# motor-shield.net
KiCad netlist of a schematic drawn in EAGLE
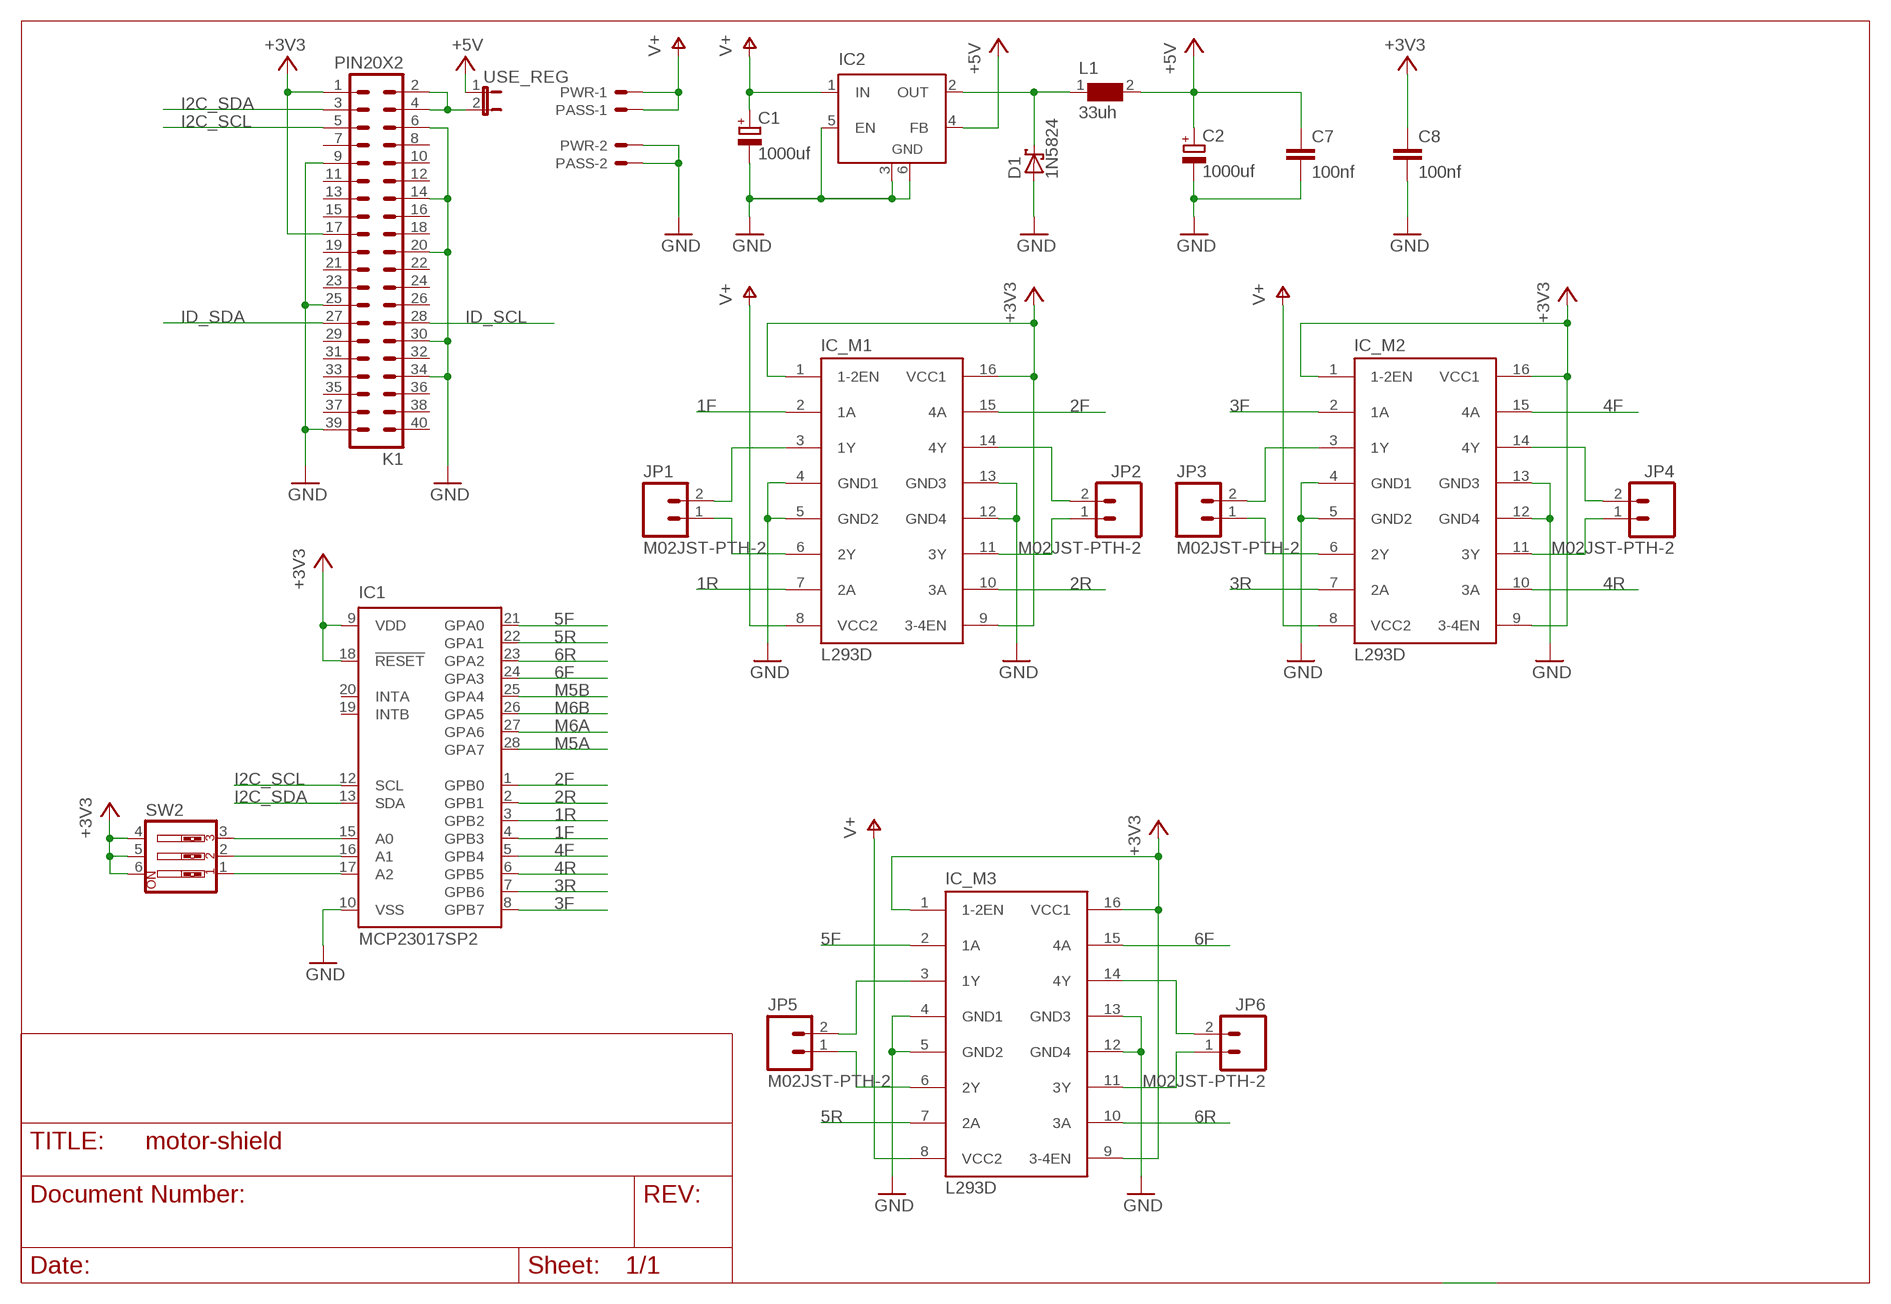
[diagram p0: schematic, sheet 1]

(export (version "E")
  (design (tool "Eeschema 10.0.6"))
  (components
    (comp (ref "C1")
      (value "1000uf")
      (footprint "eagle-import:E2,5-6")
      (libsource (lib "eagle-import") (part "CPOL-EUE2.5-6"))
    )
    (comp (ref "C2")
      (value "1000uf")
      (footprint "eagle-import:E2,5-7")
      (libsource (lib "eagle-import") (part "CPOL-EUE2.5-7"))
    )
    (comp (ref "C7")
      (value "100nf")
      (footprint "eagle-import:C025-030X050")
      (libsource (lib "eagle-import") (part "C-EU025-030X050"))
    )
    (comp (ref "C8")
      (value "100nf")
      (footprint "eagle-import:C025-030X050")
      (libsource (lib "eagle-import") (part "C-EU025-030X050"))
    )
    (comp (ref "D1")
      (value "1N5824")
      (footprint "eagle-import:DO41-7.6")
      (libsource (lib "eagle-import") (part "1N5817-B"))
    )
    (comp (ref "IC1")
      (value "MCP23017SP2")
      (footprint "eagle-import:DIL28-3-ROUND")
      (libsource (lib "eagle-import") (part "MCP23017SP2"))
    )
    (comp (ref "IC2")
      (value "LM2596S")
      (footprint "eagle-import:TO263-5")
      (libsource (lib "eagle-import") (part "LM2596S"))
    )
    (comp (ref "IC_M1")
      (value "L293D")
      (footprint "eagle-import:DIL16")
      (libsource (lib "eagle-import") (part "L293D"))
    )
    (comp (ref "IC_M2")
      (value "L293D")
      (footprint "eagle-import:DIL16")
      (libsource (lib "eagle-import") (part "L293D"))
    )
    (comp (ref "IC_M3")
      (value "L293D")
      (footprint "eagle-import:DIL16")
      (libsource (lib "eagle-import") (part "L293D"))
    )
    (comp (ref "JP1")
      (value "M02JST-PTH-2")
      (footprint "eagle-import:JST-2-PTH")
      (libsource (lib "eagle-import") (part "M02JST-PTH-2"))
    )
    (comp (ref "JP2")
      (value "M02JST-PTH-2")
      (footprint "eagle-import:JST-2-PTH")
      (libsource (lib "eagle-import") (part "M02JST-PTH-2"))
    )
    (comp (ref "JP3")
      (value "M02JST-PTH-2")
      (footprint "eagle-import:JST-2-PTH")
      (libsource (lib "eagle-import") (part "M02JST-PTH-2"))
    )
    (comp (ref "JP4")
      (value "M02JST-PTH-2")
      (footprint "eagle-import:JST-2-PTH")
      (libsource (lib "eagle-import") (part "M02JST-PTH-2"))
    )
    (comp (ref "JP5")
      (value "M02JST-PTH-2")
      (footprint "eagle-import:JST-2-PTH")
      (libsource (lib "eagle-import") (part "M02JST-PTH-2"))
    )
    (comp (ref "JP6")
      (value "M02JST-PTH-2")
      (footprint "eagle-import:JST-2-PTH")
      (libsource (lib "eagle-import") (part "M02JST-PTH-2"))
    )
    (comp (ref "K1")
      (value "PIN20X2")
      (footprint "eagle-import:PIN_20X2")
      (libsource (lib "eagle-import") (part "PIN20X2"))
    )
    (comp (ref "L1")
      (value "33uh")
      (footprint "eagle-import:WE-PD_1260_1245_1280_1210")
      (fields (field (name "MPN") "744770133"))
      (libsource (lib "eagle-import") (part "WE-PD_1260/1245/1280/1210-744770133"))
    )
    (comp (ref "PASS")
      (value "22-05-7028-02")
      (footprint "eagle-import:7395-02")
      (libsource (lib "eagle-import") (part "22-?-0205-7028"))
    )
    (comp (ref "PWR")
      (value "22-05-7028-02")
      (footprint "eagle-import:7395-02")
      (libsource (lib "eagle-import") (part "22-?-0205-7028"))
    )
    (comp (ref "SW2")
      (value "SW_DIP-3")
      (footprint "eagle-import:EDG-03")
      (libsource (lib "eagle-import") (part "SW_DIP-3"))
    )
    (comp (ref "USE_REG")
      (value "JP1E")
      (footprint "eagle-import:JP1")
      (libsource (lib "eagle-import") (part "JP1E"))
    )
  )
  (nets
    (net (code "1") (name "+3V3") (class "Default")
      (node (ref "C8") (pin "1") (pinfunction "1_1") (pintype "passive"))
      (node (ref "IC1") (pin "18") (pinfunction "~{RESET}_18") (pintype "input"))
      (node (ref "IC1") (pin "9") (pinfunction "VDD_9") (pintype "power_in"))
      (node (ref "IC_M1") (pin "1") (pinfunction "1-2EN_1") (pintype "input"))
      (node (ref "IC_M1") (pin "16") (pinfunction "VCC1_16") (pintype "power_in"))
      (node (ref "IC_M1") (pin "9") (pinfunction "3-4EN_9") (pintype "input"))
      (node (ref "IC_M2") (pin "1") (pinfunction "1-2EN_1") (pintype "input"))
      (node (ref "IC_M2") (pin "16") (pinfunction "VCC1_16") (pintype "power_in"))
      (node (ref "IC_M2") (pin "9") (pinfunction "3-4EN_9") (pintype "input"))
      (node (ref "IC_M3") (pin "1") (pinfunction "1-2EN_1") (pintype "input"))
      (node (ref "IC_M3") (pin "16") (pinfunction "VCC1_16") (pintype "power_in"))
      (node (ref "IC_M3") (pin "9") (pinfunction "3-4EN_9") (pintype "input"))
      (node (ref "K1") (pin "1") (pinfunction "1_1") (pintype "passive"))
      (node (ref "K1") (pin "17") (pinfunction "17_17") (pintype "passive"))
      (node (ref "SW2") (pin "4") (pinfunction "4_4") (pintype "passive"))
      (node (ref "SW2") (pin "5") (pinfunction "5_5") (pintype "passive"))
      (node (ref "SW2") (pin "6") (pinfunction "6_6") (pintype "passive"))
    )
    (net (code "2") (name "+5V") (class "Default")
      (node (ref "C2") (pin "+") (pinfunction "+_+") (pintype "passive"))
      (node (ref "C7") (pin "1") (pinfunction "1_1") (pintype "passive"))
      (node (ref "IC2") (pin "4") (pinfunction "FB_4") (pintype "input"))
      (node (ref "L1") (pin "2") (pinfunction "2_2") (pintype "passive"))
      (node (ref "USE_REG") (pin "1") (pinfunction "1_1") (pintype "passive"))
    )
    (net (code "3") (name "/1F") (class "Default")
      (node (ref "IC1") (pin "4") (pinfunction "GPB3_4") (pintype "bidirectional"))
      (node (ref "IC_M1") (pin "2") (pinfunction "1A_2") (pintype "input"))
    )
    (net (code "4") (name "/1R") (class "Default")
      (node (ref "IC1") (pin "3") (pinfunction "GPB2_3") (pintype "bidirectional"))
      (node (ref "IC_M1") (pin "7") (pinfunction "2A_7") (pintype "input"))
    )
    (net (code "5") (name "/2F") (class "Default")
      (node (ref "IC1") (pin "1") (pinfunction "GPB0_1") (pintype "bidirectional"))
      (node (ref "IC_M1") (pin "15") (pinfunction "4A_15") (pintype "input"))
    )
    (net (code "6") (name "/2R") (class "Default")
      (node (ref "IC1") (pin "2") (pinfunction "GPB1_2") (pintype "bidirectional"))
      (node (ref "IC_M1") (pin "10") (pinfunction "3A_10") (pintype "input"))
    )
    (net (code "7") (name "/3F") (class "Default")
      (node (ref "IC1") (pin "8") (pinfunction "GPB7_8") (pintype "bidirectional"))
      (node (ref "IC_M2") (pin "2") (pinfunction "1A_2") (pintype "input"))
    )
    (net (code "8") (name "/3R") (class "Default")
      (node (ref "IC1") (pin "7") (pinfunction "GPB6_7") (pintype "bidirectional"))
      (node (ref "IC_M2") (pin "7") (pinfunction "2A_7") (pintype "input"))
    )
    (net (code "9") (name "/4F") (class "Default")
      (node (ref "IC1") (pin "5") (pinfunction "GPB4_5") (pintype "bidirectional"))
      (node (ref "IC_M2") (pin "15") (pinfunction "4A_15") (pintype "input"))
    )
    (net (code "10") (name "/4R") (class "Default")
      (node (ref "IC1") (pin "6") (pinfunction "GPB5_6") (pintype "bidirectional"))
      (node (ref "IC_M2") (pin "10") (pinfunction "3A_10") (pintype "input"))
    )
    (net (code "11") (name "/5F") (class "Default")
      (node (ref "IC1") (pin "21") (pinfunction "GPA0_21") (pintype "bidirectional"))
      (node (ref "IC_M3") (pin "2") (pinfunction "1A_2") (pintype "input"))
    )
    (net (code "12") (name "/5R") (class "Default")
      (node (ref "IC1") (pin "22") (pinfunction "GPA1_22") (pintype "bidirectional"))
      (node (ref "IC_M3") (pin "7") (pinfunction "2A_7") (pintype "input"))
    )
    (net (code "13") (name "/6F") (class "Default")
      (node (ref "IC1") (pin "24") (pinfunction "GPA3_24") (pintype "bidirectional"))
      (node (ref "IC_M3") (pin "15") (pinfunction "4A_15") (pintype "input"))
    )
    (net (code "14") (name "/6R") (class "Default")
      (node (ref "IC1") (pin "23") (pinfunction "GPA2_23") (pintype "bidirectional"))
      (node (ref "IC_M3") (pin "10") (pinfunction "3A_10") (pintype "input"))
    )
    (net (code "15") (name "/I2C_SCL") (class "Default")
      (node (ref "IC1") (pin "12") (pinfunction "SCL_12") (pintype "input"))
      (node (ref "K1") (pin "5") (pinfunction "5_5") (pintype "passive"))
    )
    (net (code "16") (name "/I2C_SDA") (class "Default")
      (node (ref "IC1") (pin "13") (pinfunction "SDA_13") (pintype "bidirectional"))
      (node (ref "K1") (pin "3") (pinfunction "3_3") (pintype "passive"))
    )
    (net (code "17") (name "/ID_SCL") (class "Default")
      (node (ref "K1") (pin "28") (pinfunction "28_28") (pintype "passive"))
    )
    (net (code "18") (name "/ID_SDA") (class "Default")
      (node (ref "K1") (pin "27") (pinfunction "27_27") (pintype "passive"))
    )
    (net (code "19") (name "/M5A") (class "Default")
      (node (ref "IC1") (pin "28") (pinfunction "GPA7_28") (pintype "bidirectional"))
    )
    (net (code "20") (name "/M5B") (class "Default")
      (node (ref "IC1") (pin "25") (pinfunction "GPA4_25") (pintype "bidirectional"))
    )
    (net (code "21") (name "/M6A") (class "Default")
      (node (ref "IC1") (pin "27") (pinfunction "GPA6_27") (pintype "bidirectional"))
    )
    (net (code "22") (name "/M6B") (class "Default")
      (node (ref "IC1") (pin "26") (pinfunction "GPA5_26") (pintype "bidirectional"))
    )
    (net (code "23") (name "GND") (class "Default")
      (node (ref "C1") (pin "-") (pinfunction "-_-") (pintype "passive"))
      (node (ref "C2") (pin "-") (pinfunction "-_-") (pintype "passive"))
      (node (ref "C7") (pin "2") (pinfunction "2_2") (pintype "passive"))
      (node (ref "C8") (pin "2") (pinfunction "2_2") (pintype "passive"))
      (node (ref "D1") (pin "A") (pinfunction "A_A") (pintype "passive"))
      (node (ref "IC1") (pin "10") (pinfunction "VSS_10") (pintype "power_in"))
      (node (ref "IC2") (pin "3") (pinfunction "GND_3") (pintype "power_in"))
      (node (ref "IC2") (pin "5") (pinfunction "EN_5") (pintype "input"))
      (node (ref "IC2") (pin "6") (pinfunction "GND_6") (pintype "power_in"))
      (node (ref "IC_M1") (pin "12") (pinfunction "GND4_12") (pintype "power_in"))
      (node (ref "IC_M1") (pin "13") (pinfunction "GND3_13") (pintype "power_in"))
      (node (ref "IC_M1") (pin "4") (pinfunction "GND1_4") (pintype "power_in"))
      (node (ref "IC_M1") (pin "5") (pinfunction "GND2_5") (pintype "power_in"))
      (node (ref "IC_M2") (pin "12") (pinfunction "GND4_12") (pintype "power_in"))
      (node (ref "IC_M2") (pin "13") (pinfunction "GND3_13") (pintype "power_in"))
      (node (ref "IC_M2") (pin "4") (pinfunction "GND1_4") (pintype "power_in"))
      (node (ref "IC_M2") (pin "5") (pinfunction "GND2_5") (pintype "power_in"))
      (node (ref "IC_M3") (pin "12") (pinfunction "GND4_12") (pintype "power_in"))
      (node (ref "IC_M3") (pin "13") (pinfunction "GND3_13") (pintype "power_in"))
      (node (ref "IC_M3") (pin "4") (pinfunction "GND1_4") (pintype "power_in"))
      (node (ref "IC_M3") (pin "5") (pinfunction "GND2_5") (pintype "power_in"))
      (node (ref "K1") (pin "14") (pinfunction "14_14") (pintype "passive"))
      (node (ref "K1") (pin "20") (pinfunction "20_20") (pintype "passive"))
      (node (ref "K1") (pin "25") (pinfunction "25_25") (pintype "passive"))
      (node (ref "K1") (pin "30") (pinfunction "30_30") (pintype "passive"))
      (node (ref "K1") (pin "34") (pinfunction "34_34") (pintype "passive"))
      (node (ref "K1") (pin "39") (pinfunction "39_39") (pintype "passive"))
      (node (ref "K1") (pin "6") (pinfunction "6_6") (pintype "passive"))
      (node (ref "K1") (pin "9") (pinfunction "9_9") (pintype "passive"))
      (node (ref "PASS") (pin "2") (pinfunction "S_2") (pintype "passive"))
      (node (ref "PWR") (pin "2") (pinfunction "S_2") (pintype "passive"))
    )
    (net (code "24") (name "Net-(IC1-A0)") (class "Default")
      (node (ref "IC1") (pin "15") (pinfunction "A0_15") (pintype "input"))
      (node (ref "SW2") (pin "3") (pinfunction "3_3") (pintype "passive"))
    )
    (net (code "25") (name "Net-(IC1-A1)") (class "Default")
      (node (ref "IC1") (pin "16") (pinfunction "A1_16") (pintype "input"))
      (node (ref "SW2") (pin "2") (pinfunction "2_2") (pintype "passive"))
    )
    (net (code "26") (name "Net-(IC1-A2)") (class "Default")
      (node (ref "IC1") (pin "17") (pinfunction "A2_17") (pintype "input"))
      (node (ref "SW2") (pin "1") (pinfunction "1_1") (pintype "passive"))
    )
    (net (code "27") (name "Net-(IC2-OUT)") (class "Default")
      (node (ref "D1") (pin "C") (pinfunction "C_C") (pintype "passive"))
      (node (ref "IC2") (pin "2") (pinfunction "OUT_2") (pintype "output"))
      (node (ref "L1") (pin "1") (pinfunction "1_1") (pintype "passive"))
    )
    (net (code "28") (name "Net-(IC_M1-1Y)") (class "Default")
      (node (ref "IC_M1") (pin "3") (pinfunction "1Y_3") (pintype "output"))
      (node (ref "JP1") (pin "2") (pinfunction "2_2") (pintype "passive"))
    )
    (net (code "29") (name "Net-(IC_M1-2Y)") (class "Default")
      (node (ref "IC_M1") (pin "6") (pinfunction "2Y_6") (pintype "output"))
      (node (ref "JP1") (pin "1") (pinfunction "1_1") (pintype "passive"))
    )
    (net (code "30") (name "Net-(IC_M1-3Y)") (class "Default")
      (node (ref "IC_M1") (pin "11") (pinfunction "3Y_11") (pintype "output"))
      (node (ref "JP2") (pin "1") (pinfunction "1_1") (pintype "passive"))
    )
    (net (code "31") (name "Net-(IC_M1-4Y)") (class "Default")
      (node (ref "IC_M1") (pin "14") (pinfunction "4Y_14") (pintype "output"))
      (node (ref "JP2") (pin "2") (pinfunction "2_2") (pintype "passive"))
    )
    (net (code "32") (name "Net-(IC_M2-1Y)") (class "Default")
      (node (ref "IC_M2") (pin "3") (pinfunction "1Y_3") (pintype "output"))
      (node (ref "JP3") (pin "2") (pinfunction "2_2") (pintype "passive"))
    )
    (net (code "33") (name "Net-(IC_M2-2Y)") (class "Default")
      (node (ref "IC_M2") (pin "6") (pinfunction "2Y_6") (pintype "output"))
      (node (ref "JP3") (pin "1") (pinfunction "1_1") (pintype "passive"))
    )
    (net (code "34") (name "Net-(IC_M2-3Y)") (class "Default")
      (node (ref "IC_M2") (pin "11") (pinfunction "3Y_11") (pintype "output"))
      (node (ref "JP4") (pin "1") (pinfunction "1_1") (pintype "passive"))
    )
    (net (code "35") (name "Net-(IC_M2-4Y)") (class "Default")
      (node (ref "IC_M2") (pin "14") (pinfunction "4Y_14") (pintype "output"))
      (node (ref "JP4") (pin "2") (pinfunction "2_2") (pintype "passive"))
    )
    (net (code "36") (name "Net-(IC_M3-1Y)") (class "Default")
      (node (ref "IC_M3") (pin "3") (pinfunction "1Y_3") (pintype "output"))
      (node (ref "JP5") (pin "2") (pinfunction "2_2") (pintype "passive"))
    )
    (net (code "37") (name "Net-(IC_M3-2Y)") (class "Default")
      (node (ref "IC_M3") (pin "6") (pinfunction "2Y_6") (pintype "output"))
      (node (ref "JP5") (pin "1") (pinfunction "1_1") (pintype "passive"))
    )
    (net (code "38") (name "Net-(IC_M3-3Y)") (class "Default")
      (node (ref "IC_M3") (pin "11") (pinfunction "3Y_11") (pintype "output"))
      (node (ref "JP6") (pin "1") (pinfunction "1_1") (pintype "passive"))
    )
    (net (code "39") (name "Net-(IC_M3-4Y)") (class "Default")
      (node (ref "IC_M3") (pin "14") (pinfunction "4Y_14") (pintype "output"))
      (node (ref "JP6") (pin "2") (pinfunction "2_2") (pintype "passive"))
    )
    (net (code "40") (name "Net-(K1-Pad2)") (class "Default")
      (node (ref "K1") (pin "2") (pinfunction "2_2") (pintype "passive"))
      (node (ref "K1") (pin "4") (pinfunction "4_4") (pintype "passive"))
      (node (ref "USE_REG") (pin "2") (pinfunction "2_2") (pintype "passive"))
    )
    (net (code "41") (name "V+") (class "Default")
      (node (ref "C1") (pin "+") (pinfunction "+_+") (pintype "passive"))
      (node (ref "IC2") (pin "1") (pinfunction "IN_1") (pintype "input"))
      (node (ref "IC_M1") (pin "8") (pinfunction "VCC2_8") (pintype "power_in"))
      (node (ref "IC_M2") (pin "8") (pinfunction "VCC2_8") (pintype "power_in"))
      (node (ref "IC_M3") (pin "8") (pinfunction "VCC2_8") (pintype "power_in"))
      (node (ref "PASS") (pin "1") (pinfunction "S_1") (pintype "passive"))
      (node (ref "PWR") (pin "1") (pinfunction "S_1") (pintype "passive"))
    )
    (net (code "42") (name "unconnected-(IC1-INTA-Pad20)") (class "Default")
      (node (ref "IC1") (pin "20") (pinfunction "INTA_20") (pintype "output"))
    )
    (net (code "43") (name "unconnected-(IC1-INTB-Pad19)") (class "Default")
      (node (ref "IC1") (pin "19") (pinfunction "INTB_19") (pintype "output"))
    )
    (net (code "44") (name "unconnected-(K1-Pad7)") (class "Default")
      (node (ref "K1") (pin "7") (pinfunction "7_7") (pintype "passive"))
    )
    (net (code "45") (name "unconnected-(K1-Pad8)") (class "Default")
      (node (ref "K1") (pin "8") (pinfunction "8_8") (pintype "passive"))
    )
    (net (code "46") (name "unconnected-(K1-Pad10)") (class "Default")
      (node (ref "K1") (pin "10") (pinfunction "10_10") (pintype "passive"))
    )
    (net (code "47") (name "unconnected-(K1-Pad11)") (class "Default")
      (node (ref "K1") (pin "11") (pinfunction "11_11") (pintype "passive"))
    )
    (net (code "48") (name "unconnected-(K1-Pad12)") (class "Default")
      (node (ref "K1") (pin "12") (pinfunction "12_12") (pintype "passive"))
    )
    (net (code "49") (name "unconnected-(K1-Pad13)") (class "Default")
      (node (ref "K1") (pin "13") (pinfunction "13_13") (pintype "passive"))
    )
    (net (code "50") (name "unconnected-(K1-Pad15)") (class "Default")
      (node (ref "K1") (pin "15") (pinfunction "15_15") (pintype "passive"))
    )
    (net (code "51") (name "unconnected-(K1-Pad16)") (class "Default")
      (node (ref "K1") (pin "16") (pinfunction "16_16") (pintype "passive"))
    )
    (net (code "52") (name "unconnected-(K1-Pad18)") (class "Default")
      (node (ref "K1") (pin "18") (pinfunction "18_18") (pintype "passive"))
    )
    (net (code "53") (name "unconnected-(K1-Pad19)") (class "Default")
      (node (ref "K1") (pin "19") (pinfunction "19_19") (pintype "passive"))
    )
    (net (code "54") (name "unconnected-(K1-Pad21)") (class "Default")
      (node (ref "K1") (pin "21") (pinfunction "21_21") (pintype "passive"))
    )
    (net (code "55") (name "unconnected-(K1-Pad22)") (class "Default")
      (node (ref "K1") (pin "22") (pinfunction "22_22") (pintype "passive"))
    )
    (net (code "56") (name "unconnected-(K1-Pad23)") (class "Default")
      (node (ref "K1") (pin "23") (pinfunction "23_23") (pintype "passive"))
    )
    (net (code "57") (name "unconnected-(K1-Pad24)") (class "Default")
      (node (ref "K1") (pin "24") (pinfunction "24_24") (pintype "passive"))
    )
    (net (code "58") (name "unconnected-(K1-Pad26)") (class "Default")
      (node (ref "K1") (pin "26") (pinfunction "26_26") (pintype "passive"))
    )
    (net (code "59") (name "unconnected-(K1-Pad29)") (class "Default")
      (node (ref "K1") (pin "29") (pinfunction "29_29") (pintype "passive"))
    )
    (net (code "60") (name "unconnected-(K1-Pad31)") (class "Default")
      (node (ref "K1") (pin "31") (pinfunction "31_31") (pintype "passive"))
    )
    (net (code "61") (name "unconnected-(K1-Pad32)") (class "Default")
      (node (ref "K1") (pin "32") (pinfunction "32_32") (pintype "passive"))
    )
    (net (code "62") (name "unconnected-(K1-Pad33)") (class "Default")
      (node (ref "K1") (pin "33") (pinfunction "33_33") (pintype "passive"))
    )
    (net (code "63") (name "unconnected-(K1-Pad35)") (class "Default")
      (node (ref "K1") (pin "35") (pinfunction "35_35") (pintype "passive"))
    )
    (net (code "64") (name "unconnected-(K1-Pad36)") (class "Default")
      (node (ref "K1") (pin "36") (pinfunction "36_36") (pintype "passive"))
    )
    (net (code "65") (name "unconnected-(K1-Pad37)") (class "Default")
      (node (ref "K1") (pin "37") (pinfunction "37_37") (pintype "passive"))
    )
    (net (code "66") (name "unconnected-(K1-Pad38)") (class "Default")
      (node (ref "K1") (pin "38") (pinfunction "38_38") (pintype "passive"))
    )
    (net (code "67") (name "unconnected-(K1-Pad40)") (class "Default")
      (node (ref "K1") (pin "40") (pinfunction "40_40") (pintype "passive"))
    )
  )
)
